# Switch_Led.net
KiCad netlist of a schematic drawn in Altium Designer
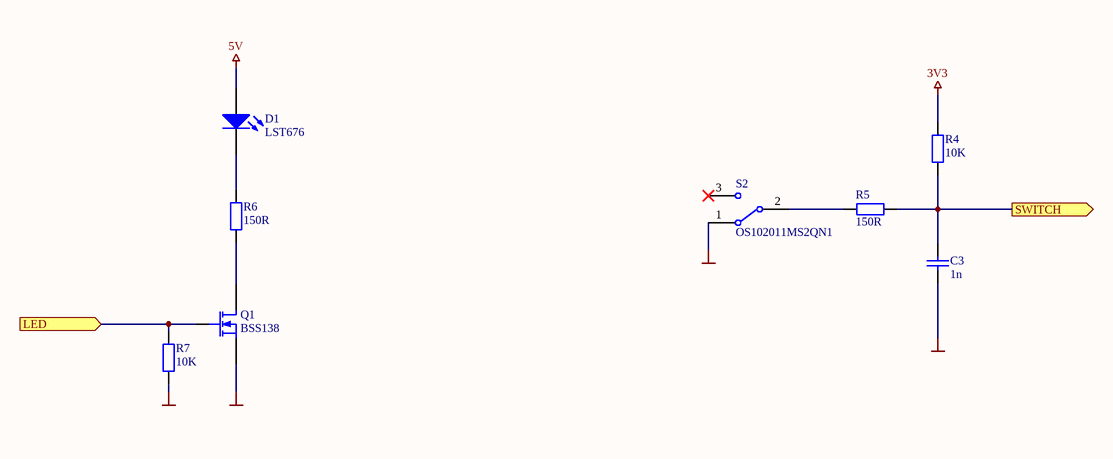
[diagram p0: Switch_Led.SchDoc]

(export (version "E")
  (design (tool "Eeschema 10.0.6"))
  (components
    (comp (ref "C3")
      (value "1n")
      (footprint "SMD_CAPC1608X08N")
      (description "CERCAP 1n 100V 1% NP0/C0G 0603")
      (fields
        (field (name "MANUFACTURER") "KEMET")
        (field (name "MANUFACTURER PART NUMBER") "C0603C102F1GAC7867")
      )
      (libsource (lib "ETHZ Vault") (part "Cap"))
    )
    (comp (ref "D1")
      (value "LST676")
      (footprint "2-PLCC")
      (description "LED RED 30mA 2V 3x3.4mm")
      (fields
        (field (name "MANUFACTURER") "OSRAM Opto Semiconductors Inc.")
        (field (name "MANUFACTURER PART NUMBER") "LS T676-R1S1-1-Z")
      )
      (libsource (lib "ETHZ Vault") (part "Diode LED"))
    )
    (comp (ref "Q1")
      (value "BSS138")
      (footprint "SOT323 SC70")
      (description "MOSFET N 0.2A 50V SOT323")
      (fields
        (field (name "MANUFACTURER2 PART NUMBER") "BSS138W-TP")
        (field (name "MANUFACTURER") "Diodes Incorporated")
      )
      (libsource (lib "ETHZ Vault") (part "MOSFET-N"))
    )
    (comp (ref "R4")
      (value "10K")
      (footprint "SMD_RESC1608X05N")
      (description "RES 10K 100mW 1% 0603")
      (fields
        (field (name "MANUFACTURER") "YAEGO")
        (field (name "MANUFACTURER PART NUMBER") "RC0603FR-0710KL")
      )
      (libsource (lib "ETHZ Vault") (part "Res"))
    )
    (comp (ref "R5")
      (value "150R")
      (footprint "SMD_RESC1608X05N")
      (description "RES 150R 100mW 1% 0603")
      (fields
        (field (name "MANUFACTURER") "YAEGO")
        (field (name "MANUFACTURER PART NUMBER") "RC0603FR-07150RL")
      )
      (libsource (lib "ETHZ Vault") (part "Res"))
    )
    (comp (ref "R6")
      (value "150R")
      (footprint "SMD_RESC1608X05N")
      (description "RES 150R 100mW 1% 0603")
      (fields
        (field (name "MANUFACTURER") "YAEGO")
        (field (name "MANUFACTURER PART NUMBER") "RC0603FR-07150RL")
      )
      (libsource (lib "ETHZ Vault") (part "Res"))
    )
    (comp (ref "R7")
      (value "10K")
      (footprint "SMD_RESC1608X05N")
      (description "RES 10K 100mW 1% 0603")
      (fields
        (field (name "MANUFACTURER") "YAEGO")
        (field (name "MANUFACTURER PART NUMBER") "RC0603FR-0710KL")
      )
      (libsource (lib "ETHZ Vault") (part "Res"))
    )
    (comp (ref "S2")
      (value "OS102011MS2QN1")
      (footprint "THT_SLIDESWITCH_86X43")
      (description "SWITCH SPDT 12V 0.1A 4.3x8.6mm")
      (fields (field (name "MANUFACTURER") "C&K"))
      (libsource (lib "ETHZ Vault") (part "SW SPDT"))
    )
  )
  (nets
    (net (code "1") (name "/LED") (class "Default")
      (node (ref "Q1") (pin "1") (pinfunction "G_1") (pintype "passive"))
      (node (ref "R7") (pin "2") (pinfunction "2_2") (pintype "passive"))
    )
    (net (code "2") (name "/SWITCH") (class "Default")
      (node (ref "C3") (pin "2") (pinfunction "2_2") (pintype "passive"))
      (node (ref "R4") (pin "1") (pinfunction "1_1") (pintype "passive"))
      (node (ref "R5") (pin "1") (pinfunction "1_1") (pintype "passive"))
    )
    (net (code "3") (name "3V3") (class "Default")
      (node (ref "R4") (pin "2") (pinfunction "2_2") (pintype "passive"))
    )
    (net (code "4") (name "5V") (class "Default")
      (node (ref "D1") (pin "1") (pinfunction "A_1") (pintype "passive"))
    )
    (net (code "5") (name "GND") (class "Default")
      (node (ref "C3") (pin "1") (pinfunction "1_1") (pintype "passive"))
      (node (ref "Q1") (pin "2") (pinfunction "S_2") (pintype "passive"))
      (node (ref "R7") (pin "1") (pinfunction "1_1") (pintype "passive"))
      (node (ref "S2") (pin "1") (pinfunction "1_1") (pintype "passive"))
    )
    (net (code "6") (name "Net-(D1-K)") (class "Default")
      (node (ref "D1") (pin "2") (pinfunction "K_2") (pintype "passive"))
      (node (ref "R6") (pin "2") (pinfunction "2_2") (pintype "passive"))
    )
    (net (code "7") (name "Net-(Q1-D)") (class "Default")
      (node (ref "Q1") (pin "3") (pinfunction "D_3") (pintype "passive"))
      (node (ref "R6") (pin "1") (pinfunction "1_1") (pintype "passive"))
    )
    (net (code "8") (name "Net-(R5-Pad2)") (class "Default")
      (node (ref "R5") (pin "2") (pinfunction "2_2") (pintype "passive"))
      (node (ref "S2") (pin "2") (pinfunction "2_2") (pintype "passive"))
    )
    (net (code "9") (name "unconnected-(S2-Pad3)") (class "Default")
      (node (ref "S2") (pin "3") (pinfunction "3_3") (pintype "passive+no_connect"))
    )
  )
)
